# schematic.net
KiCad netlist of a schematic drawn in Altium Designer
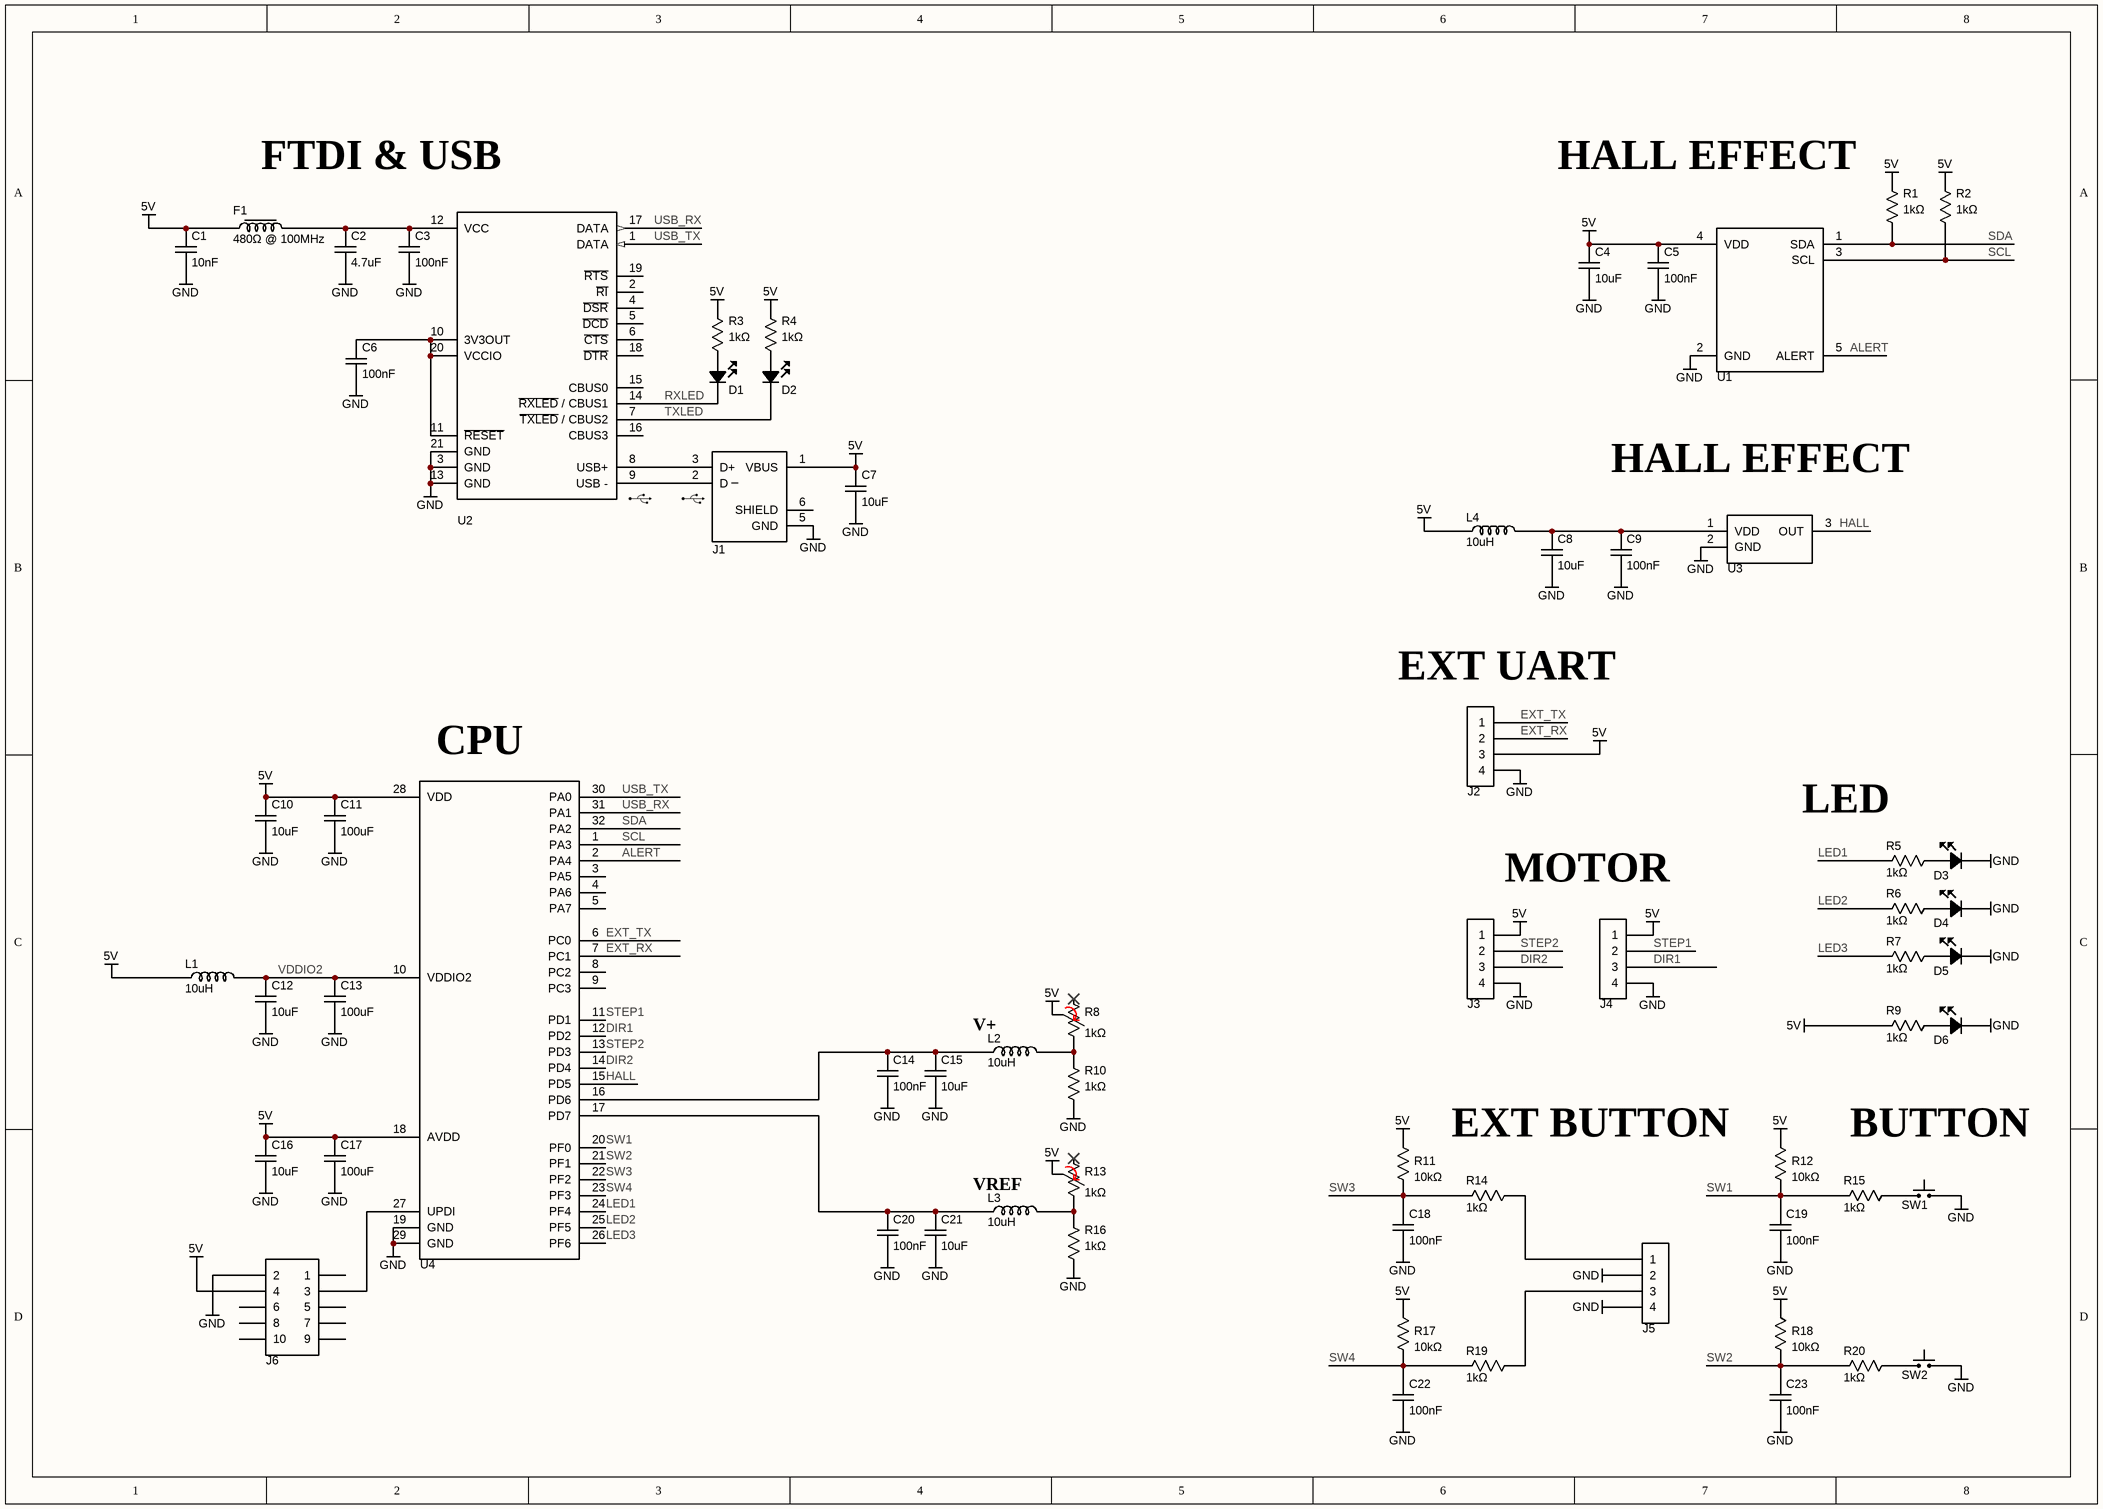
[diagram p0: schematic.SchDoc]

(export (version "E")
  (design (tool "Eeschema 10.0.6"))
  (components
    (comp (ref "C1")
      (value "10nF")
      (footprint "capacitor 0603")
      (description "Capacitor 0603")
      (fields (field (name "Comment") "passive_5"))
      (libsource (lib "passive") (part "passive_5"))
    )
    (comp (ref "C2")
      (value "4.7uF")
      (footprint "capacitor 0603")
      (description "Capacitor 0603")
      (fields (field (name "Comment") "passive_5"))
      (libsource (lib "passive") (part "passive_5"))
    )
    (comp (ref "C3")
      (value "100nF")
      (footprint "capacitor 0603")
      (description "Capacitor 0603")
      (fields (field (name "Comment") "passive_5"))
      (libsource (lib "passive") (part "passive_5"))
    )
    (comp (ref "C4")
      (value "10uF")
      (footprint "capacitor 0603")
      (description "Capacitor 0603")
      (fields (field (name "Comment") "passive_5"))
      (libsource (lib "passive") (part "passive_5"))
    )
    (comp (ref "C5")
      (value "100nF")
      (footprint "capacitor 0603")
      (description "Capacitor 0603")
      (fields (field (name "Comment") "passive_5"))
      (libsource (lib "passive") (part "passive_5"))
    )
    (comp (ref "C6")
      (value "100nF")
      (footprint "capacitor 0603")
      (description "Capacitor 0603")
      (fields (field (name "Comment") "passive_5"))
      (libsource (lib "passive") (part "passive_5"))
    )
    (comp (ref "C7")
      (value "10uF")
      (footprint "capacitor 0603")
      (description "Capacitor 0603")
      (fields (field (name "Comment") "passive_5"))
      (libsource (lib "passive") (part "passive_5"))
    )
    (comp (ref "C8")
      (value "10uF")
      (footprint "capacitor 0603")
      (description "Capacitor 0603")
      (fields (field (name "Comment") "passive_5"))
      (libsource (lib "passive") (part "passive_5"))
    )
    (comp (ref "C9")
      (value "100nF")
      (footprint "capacitor 0603")
      (description "Capacitor 0603")
      (fields (field (name "Comment") "passive_5"))
      (libsource (lib "passive") (part "passive_5"))
    )
    (comp (ref "C10")
      (value "10uF")
      (footprint "capacitor 0603")
      (description "Capacitor 0603")
      (fields (field (name "Comment") "passive_5"))
      (libsource (lib "passive") (part "passive_5"))
    )
    (comp (ref "C11")
      (value "100uF")
      (footprint "capacitor 0603")
      (description "Capacitor 0603")
      (fields (field (name "Comment") "passive_5"))
      (libsource (lib "passive") (part "passive_5"))
    )
    (comp (ref "C12")
      (value "10uF")
      (footprint "capacitor 0603")
      (description "Capacitor 0603")
      (fields (field (name "Comment") "passive_5"))
      (libsource (lib "passive") (part "passive_5"))
    )
    (comp (ref "C13")
      (value "100uF")
      (footprint "capacitor 0603")
      (description "Capacitor 0603")
      (fields (field (name "Comment") "passive_5"))
      (libsource (lib "passive") (part "passive_5"))
    )
    (comp (ref "C14")
      (value "100nF")
      (footprint "capacitor 0603")
      (description "Capacitor 0603")
      (fields (field (name "Comment") "passive_5"))
      (libsource (lib "passive") (part "passive_5"))
    )
    (comp (ref "C15")
      (value "10uF")
      (footprint "capacitor 0603")
      (description "Capacitor 0603")
      (fields (field (name "Comment") "passive_5"))
      (libsource (lib "passive") (part "passive_5"))
    )
    (comp (ref "C16")
      (value "10uF")
      (footprint "capacitor 0603")
      (description "Capacitor 0603")
      (fields (field (name "Comment") "passive_5"))
      (libsource (lib "passive") (part "passive_5"))
    )
    (comp (ref "C17")
      (value "100uF")
      (footprint "capacitor 0603")
      (description "Capacitor 0603")
      (fields (field (name "Comment") "passive_5"))
      (libsource (lib "passive") (part "passive_5"))
    )
    (comp (ref "C18")
      (value "100nF")
      (footprint "capacitor 0603")
      (description "Capacitor 0603")
      (fields (field (name "Comment") "passive_5"))
      (libsource (lib "passive") (part "passive_5"))
    )
    (comp (ref "C19")
      (value "100nF")
      (footprint "capacitor 0603")
      (description "Capacitor 0603")
      (fields (field (name "Comment") "passive_5"))
      (libsource (lib "passive") (part "passive_5"))
    )
    (comp (ref "C20")
      (value "100nF")
      (footprint "capacitor 0603")
      (description "Capacitor 0603")
      (fields (field (name "Comment") "passive_5"))
      (libsource (lib "passive") (part "passive_5"))
    )
    (comp (ref "C21")
      (value "10uF")
      (footprint "capacitor 0603")
      (description "Capacitor 0603")
      (fields (field (name "Comment") "passive_5"))
      (libsource (lib "passive") (part "passive_5"))
    )
    (comp (ref "C22")
      (value "100nF")
      (footprint "capacitor 0603")
      (description "Capacitor 0603")
      (fields (field (name "Comment") "passive_5"))
      (libsource (lib "passive") (part "passive_5"))
    )
    (comp (ref "C23")
      (value "100nF")
      (footprint "capacitor 0603")
      (description "Capacitor 0603")
      (fields (field (name "Comment") "passive_5"))
      (libsource (lib "passive") (part "passive_5"))
    )
    (comp (ref "D1")
      (value "LED Red")
      (footprint "LED 0603 red")
      (description "LED 0603 red")
      (libsource (lib "diode") (part "diode_0"))
    )
    (comp (ref "D2")
      (value "LED Red")
      (footprint "LED 0603 red")
      (description "LED 0603 red")
      (libsource (lib "diode") (part "diode_0"))
    )
    (comp (ref "D3")
      (value "LED Red")
      (footprint "LED 0603 red")
      (description "LED 0603 red")
      (libsource (lib "diode") (part "diode_0"))
    )
    (comp (ref "D4")
      (value "LED Red")
      (footprint "LED 0603 red")
      (description "LED 0603 red")
      (libsource (lib "diode") (part "diode_0"))
    )
    (comp (ref "D5")
      (value "LED Red")
      (footprint "LED 0603 red")
      (description "LED 0603 red")
      (libsource (lib "diode") (part "diode_0"))
    )
    (comp (ref "D6")
      (value "LED Red")
      (footprint "LED 0603 red")
      (description "LED 0603 red")
      (libsource (lib "diode") (part "diode_0"))
    )
    (comp (ref "F1")
      (value "480Ω @ 100MHz")
      (footprint "ferrit bead 0603")
      (description "Ferrite bead 0603")
      (fields (field (name "Comment") "passive_8"))
      (libsource (lib "passive") (part "passive_8"))
    )
    (comp (ref "J1")
      (value "USB micro B")
      (footprint "USB mico B female")
      (description "USB micro B (2.0)")
      (libsource (lib "connector") (part "connector_34"))
    )
    (comp (ref "J2")
      (value "Header 2.54mm")
      (footprint "TB001-500-04BE")
      (description "Screw Terminal")
      (libsource (lib "connector") (part "connector_53"))
    )
    (comp (ref "J3")
      (value "Header 2.54mm")
      (footprint "TB001-500-04BE")
      (description "Screw Terminal")
      (libsource (lib "connector") (part "connector_53"))
    )
    (comp (ref "J4")
      (value "Header 2.54mm")
      (footprint "TB001-500-04BE")
      (description "Screw Terminal")
      (libsource (lib "connector") (part "connector_53"))
    )
    (comp (ref "J5")
      (value "Header 2.54mm")
      (footprint "TB001-500-04BE")
      (description "Screw Terminal")
      (libsource (lib "") (part "connector_53_1"))
    )
    (comp (ref "J6")
      (value "Header 1.27mm")
      (footprint "header male 2x5, pitch 1.27mm")
      (description "Header male 2x5, pitch 1.27mm")
      (libsource (lib "connector") (part "connector_17"))
    )
    (comp (ref "L1")
      (value "10uH")
      (footprint "inductor 0603")
      (description "Inductor 0603")
      (fields (field (name "Comment") "passive_9"))
      (libsource (lib "") (part "passive_9_1"))
    )
    (comp (ref "L2")
      (value "10uH")
      (footprint "inductor 0603")
      (description "Inductor 0603")
      (fields (field (name "Comment") "passive_9"))
      (libsource (lib "passive") (part "passive_9"))
    )
    (comp (ref "L3")
      (value "10uH")
      (footprint "inductor 0603")
      (description "Inductor 0603")
      (fields (field (name "Comment") "passive_9"))
      (libsource (lib "passive") (part "passive_9"))
    )
    (comp (ref "L4")
      (value "10uH")
      (footprint "inductor 0603")
      (description "Inductor 0603")
      (fields (field (name "Comment") "passive_9"))
      (libsource (lib "") (part "passive_9_1"))
    )
    (comp (ref "R1")
      (value "1kΩ")
      (footprint "resistor 0603")
      (description "Resistor 0603")
      (fields (field (name "Comment") "passive_2"))
      (libsource (lib "passive") (part "passive_2"))
    )
    (comp (ref "R2")
      (value "1kΩ")
      (footprint "resistor 0603")
      (description "Resistor 0603")
      (fields (field (name "Comment") "passive_2"))
      (libsource (lib "passive") (part "passive_2"))
    )
    (comp (ref "R3")
      (value "1kΩ")
      (footprint "resistor 0603")
      (description "Resistor 0603")
      (fields (field (name "Comment") "passive_2"))
      (libsource (lib "passive") (part "passive_2"))
    )
    (comp (ref "R4")
      (value "1kΩ")
      (footprint "resistor 0603")
      (description "Resistor 0603")
      (fields (field (name "Comment") "passive_2"))
      (libsource (lib "passive") (part "passive_2"))
    )
    (comp (ref "R5")
      (value "1kΩ")
      (footprint "resistor 0603")
      (description "Resistor 0603")
      (fields (field (name "Comment") "passive_2"))
      (libsource (lib "passive") (part "passive_2"))
    )
    (comp (ref "R6")
      (value "1kΩ")
      (footprint "resistor 0603")
      (description "Resistor 0603")
      (fields (field (name "Comment") "passive_2"))
      (libsource (lib "passive") (part "passive_2"))
    )
    (comp (ref "R7")
      (value "1kΩ")
      (footprint "resistor 0603")
      (description "Resistor 0603")
      (fields (field (name "Comment") "passive_2"))
      (libsource (lib "passive") (part "passive_2"))
    )
    (comp (ref "R8")
      (value "1kΩ")
      (footprint "POT")
      (description "Potmeter")
      (fields (field (name "Comment") "passive_13"))
      (libsource (lib "passive") (part "passive_13"))
    )
    (comp (ref "R9")
      (value "1kΩ")
      (footprint "resistor 0603")
      (description "Resistor 0603")
      (fields (field (name "Comment") "passive_2"))
      (libsource (lib "passive") (part "passive_2"))
    )
    (comp (ref "R10")
      (value "1kΩ")
      (footprint "resistor 0603")
      (description "Resistor 0603")
      (fields (field (name "Comment") "passive_2"))
      (libsource (lib "passive") (part "passive_2"))
    )
    (comp (ref "R11")
      (value "10kΩ")
      (footprint "resistor 0603")
      (description "Resistor 0603")
      (fields (field (name "Comment") "passive_2"))
      (libsource (lib "passive") (part "passive_2"))
    )
    (comp (ref "R12")
      (value "10kΩ")
      (footprint "resistor 0603")
      (description "Resistor 0603")
      (fields (field (name "Comment") "passive_2"))
      (libsource (lib "passive") (part "passive_2"))
    )
    (comp (ref "R13")
      (value "1kΩ")
      (footprint "POT")
      (description "Potmeter")
      (fields (field (name "Comment") "passive_13"))
      (libsource (lib "passive") (part "passive_13"))
    )
    (comp (ref "R14")
      (value "1kΩ")
      (footprint "resistor 0603")
      (description "Resistor 0603")
      (fields (field (name "Comment") "passive_2"))
      (libsource (lib "passive") (part "passive_2"))
    )
    (comp (ref "R15")
      (value "1kΩ")
      (footprint "resistor 0603")
      (description "Resistor 0603")
      (fields (field (name "Comment") "passive_2"))
      (libsource (lib "passive") (part "passive_2"))
    )
    (comp (ref "R16")
      (value "1kΩ")
      (footprint "resistor 0603")
      (description "Resistor 0603")
      (fields (field (name "Comment") "passive_2"))
      (libsource (lib "passive") (part "passive_2"))
    )
    (comp (ref "R17")
      (value "10kΩ")
      (footprint "resistor 0603")
      (description "Resistor 0603")
      (fields (field (name "Comment") "passive_2"))
      (libsource (lib "passive") (part "passive_2"))
    )
    (comp (ref "R18")
      (value "10kΩ")
      (footprint "resistor 0603")
      (description "Resistor 0603")
      (fields (field (name "Comment") "passive_2"))
      (libsource (lib "passive") (part "passive_2"))
    )
    (comp (ref "R19")
      (value "1kΩ")
      (footprint "resistor 0603")
      (description "Resistor 0603")
      (fields (field (name "Comment") "passive_2"))
      (libsource (lib "passive") (part "passive_2"))
    )
    (comp (ref "R20")
      (value "1kΩ")
      (footprint "resistor 0603")
      (description "Resistor 0603")
      (fields (field (name "Comment") "passive_2"))
      (libsource (lib "passive") (part "passive_2"))
    )
    (comp (ref "SW1")
      (value "sensor_3")
      (footprint "KMR621NG LFS")
      (description "Tactile switch SMD, tiny")
      (libsource (lib "sensor") (part "sensor_3"))
    )
    (comp (ref "SW2")
      (value "sensor_3")
      (footprint "KMR621NG LFS")
      (description "Tactile switch SMD, tiny")
      (libsource (lib "sensor") (part "sensor_3"))
    )
    (comp (ref "U1")
      (value "ic_14")
      (footprint "SI7210-B-00-IVR")
      (description "Hall-effect")
      (libsource (lib "integrated-circuit") (part "ic_14"))
    )
    (comp (ref "U2")
      (value "FTDI")
      (footprint "FT231XQ-R")
      (description "USB to UART converter, FTDI, single, 20 pins, QFN")
      (libsource (lib "integrated-circuit") (part "ic_1"))
    )
    (comp (ref "U3")
      (value "ic_15")
      (footprint "SS495A1")
      (description "SS495A1")
      (libsource (lib "integrated-circuit") (part "ic_15"))
    )
    (comp (ref "U4")
      (value "cpu_7")
      (footprint "AVRxxDB32")
      (description "AVRxxDB32")
      (libsource (lib "cpu") (part "cpu_7"))
    )
  )
  (nets
    (net (code "1") (name "/ALERT") (class "Default")
      (node (ref "U1") (pin "5") (pinfunction "ALERT_5") (pintype "passive"))
      (node (ref "U4") (pin "2") (pinfunction "PA4_2") (pintype "passive"))
    )
    (net (code "2") (name "/DIR1") (class "Default")
      (node (ref "J4") (pin "3") (pinfunction "3_3") (pintype "passive"))
      (node (ref "U4") (pin "12") (pinfunction "PD2_12") (pintype "passive"))
    )
    (net (code "3") (name "/DIR2") (class "Default")
      (node (ref "J3") (pin "3") (pinfunction "3_3") (pintype "passive"))
      (node (ref "U4") (pin "14") (pinfunction "PD4_14") (pintype "passive"))
    )
    (net (code "4") (name "/EXT_RX") (class "Default")
      (node (ref "J2") (pin "2") (pinfunction "2_2") (pintype "passive"))
      (node (ref "U4") (pin "7") (pinfunction "PC1_7") (pintype "passive"))
    )
    (net (code "5") (name "/EXT_TX") (class "Default")
      (node (ref "J2") (pin "1") (pinfunction "1_1") (pintype "passive"))
      (node (ref "U4") (pin "6") (pinfunction "PC0_6") (pintype "passive"))
    )
    (net (code "6") (name "/HALL") (class "Default")
      (node (ref "U3") (pin "3") (pinfunction "OUT_3") (pintype "passive"))
      (node (ref "U4") (pin "15") (pinfunction "PD5_15") (pintype "passive"))
    )
    (net (code "7") (name "/LED1") (class "Default")
      (node (ref "R5") (pin "2") (pinfunction "2_2") (pintype "passive"))
      (node (ref "U4") (pin "24") (pinfunction "PF4_24") (pintype "passive"))
    )
    (net (code "8") (name "/LED2") (class "Default")
      (node (ref "R6") (pin "2") (pinfunction "2_2") (pintype "passive"))
      (node (ref "U4") (pin "25") (pinfunction "PF5_25") (pintype "passive"))
    )
    (net (code "9") (name "/LED3") (class "Default")
      (node (ref "R7") (pin "2") (pinfunction "2_2") (pintype "passive"))
      (node (ref "U4") (pin "26") (pinfunction "PF6_26") (pintype "passive"))
    )
    (net (code "10") (name "/RXLED") (class "Default")
      (node (ref "D1") (pin "2") (pinfunction "2_2") (pintype "passive"))
      (node (ref "U2") (pin "14") (pinfunction "~{RXLED}_/_CBUS1_14") (pintype "passive"))
    )
    (net (code "11") (name "/SCL") (class "Default")
      (node (ref "R2") (pin "1") (pintype "passive"))
      (node (ref "U1") (pin "3") (pinfunction "SCL_3") (pintype "passive"))
      (node (ref "U4") (pin "1") (pinfunction "PA3_1") (pintype "passive"))
    )
    (net (code "12") (name "/SDA") (class "Default")
      (node (ref "R1") (pin "1") (pintype "passive"))
      (node (ref "U1") (pin "1") (pinfunction "SDA_1") (pintype "passive"))
      (node (ref "U4") (pin "32") (pinfunction "PA2_32") (pintype "passive"))
    )
    (net (code "13") (name "/STEP1") (class "Default")
      (node (ref "J4") (pin "2") (pinfunction "2_2") (pintype "passive"))
      (node (ref "U4") (pin "11") (pinfunction "PD1_11") (pintype "passive"))
    )
    (net (code "14") (name "/STEP2") (class "Default")
      (node (ref "J3") (pin "2") (pinfunction "2_2") (pintype "passive"))
      (node (ref "U4") (pin "13") (pinfunction "PD3_13") (pintype "passive"))
    )
    (net (code "15") (name "/SW1") (class "Default")
      (node (ref "C19") (pin "2") (pinfunction "2_2") (pintype "passive"))
      (node (ref "R12") (pin "2") (pinfunction "2_2") (pintype "passive"))
      (node (ref "R15") (pin "2") (pinfunction "2_2") (pintype "passive"))
      (node (ref "U4") (pin "20") (pinfunction "PF0_20") (pintype "passive"))
    )
    (net (code "16") (name "/SW2") (class "Default")
      (node (ref "C23") (pin "2") (pinfunction "2_2") (pintype "passive"))
      (node (ref "R18") (pin "2") (pinfunction "2_2") (pintype "passive"))
      (node (ref "R20") (pin "2") (pinfunction "2_2") (pintype "passive"))
      (node (ref "U4") (pin "21") (pinfunction "PF1_21") (pintype "passive"))
    )
    (net (code "17") (name "/SW3") (class "Default")
      (node (ref "C18") (pin "2") (pinfunction "2_2") (pintype "passive"))
      (node (ref "R11") (pin "2") (pinfunction "2_2") (pintype "passive"))
      (node (ref "R14") (pin "2") (pinfunction "2_2") (pintype "passive"))
      (node (ref "U4") (pin "22") (pinfunction "PF2_22") (pintype "passive"))
    )
    (net (code "18") (name "/SW4") (class "Default")
      (node (ref "C22") (pin "2") (pinfunction "2_2") (pintype "passive"))
      (node (ref "R17") (pin "2") (pinfunction "2_2") (pintype "passive"))
      (node (ref "R19") (pin "2") (pinfunction "2_2") (pintype "passive"))
      (node (ref "U4") (pin "23") (pinfunction "PF3_23") (pintype "passive"))
    )
    (net (code "19") (name "/TXLED") (class "Default")
      (node (ref "D2") (pin "2") (pinfunction "2_2") (pintype "passive"))
      (node (ref "U2") (pin "7") (pinfunction "~{TXLED}_/_CBUS2_7") (pintype "passive"))
    )
    (net (code "20") (name "/USB_RX") (class "Default")
      (node (ref "U2") (pin "17") (pinfunction "DATA_17") (pintype "passive"))
      (node (ref "U4") (pin "31") (pinfunction "PA1_31") (pintype "passive"))
    )
    (net (code "21") (name "/USB_TX") (class "Default")
      (node (ref "U2") (pin "1") (pinfunction "DATA_1") (pintype "passive"))
      (node (ref "U4") (pin "30") (pinfunction "PA0_30") (pintype "passive"))
    )
    (net (code "22") (name "/VDDIO2") (class "Default")
      (node (ref "C12") (pin "2") (pinfunction "2_2") (pintype "passive"))
      (node (ref "C13") (pin "2") (pinfunction "2_2") (pintype "passive"))
      (node (ref "L1") (pin "2") (pinfunction "2_2") (pintype "passive"))
      (node (ref "U4") (pin "10") (pinfunction "VDDIO2_10") (pintype "passive"))
    )
    (net (code "23") (name "5V") (class "Default")
      (node (ref "C1") (pin "2") (pinfunction "2_2") (pintype "passive"))
      (node (ref "C10") (pin "2") (pinfunction "2_2") (pintype "passive"))
      (node (ref "C11") (pin "2") (pinfunction "2_2") (pintype "passive"))
      (node (ref "C16") (pin "2") (pinfunction "2_2") (pintype "passive"))
      (node (ref "C17") (pin "2") (pinfunction "2_2") (pintype "passive"))
      (node (ref "C4") (pin "2") (pinfunction "2_2") (pintype "passive"))
      (node (ref "C5") (pin "2") (pinfunction "2_2") (pintype "passive"))
      (node (ref "C7") (pin "2") (pinfunction "2_2") (pintype "passive"))
      (node (ref "F1") (pin "1") (pintype "passive"))
      (node (ref "J1") (pin "1") (pinfunction "VBUS_1") (pintype "passive"))
      (node (ref "J2") (pin "3") (pinfunction "3_3") (pintype "passive"))
      (node (ref "J3") (pin "1") (pinfunction "1_1") (pintype "passive"))
      (node (ref "J4") (pin "1") (pinfunction "1_1") (pintype "passive"))
      (node (ref "J6") (pin "4") (pinfunction "4_4") (pintype "passive"))
      (node (ref "L1") (pin "1") (pintype "passive"))
      (node (ref "L4") (pin "1") (pintype "passive"))
      (node (ref "R1") (pin "2") (pinfunction "2_2") (pintype "passive"))
      (node (ref "R11") (pin "1") (pintype "passive"))
      (node (ref "R12") (pin "1") (pintype "passive"))
      (node (ref "R13") (pin "2") (pintype "passive"))
      (node (ref "R17") (pin "1") (pintype "passive"))
      (node (ref "R18") (pin "1") (pintype "passive"))
      (node (ref "R2") (pin "2") (pinfunction "2_2") (pintype "passive"))
      (node (ref "R3") (pin "2") (pinfunction "2_2") (pintype "passive"))
      (node (ref "R4") (pin "2") (pinfunction "2_2") (pintype "passive"))
      (node (ref "R8") (pin "2") (pintype "passive"))
      (node (ref "R9") (pin "2") (pinfunction "2_2") (pintype "passive"))
      (node (ref "U1") (pin "4") (pinfunction "VDD_4") (pintype "passive"))
      (node (ref "U4") (pin "18") (pinfunction "AVDD_18") (pintype "passive"))
      (node (ref "U4") (pin "28") (pinfunction "VDD_28") (pintype "passive"))
    )
    (net (code "24") (name "GND") (class "Default")
      (node (ref "C1") (pin "1") (pinfunction "1_1") (pintype "passive"))
      (node (ref "C10") (pin "1") (pinfunction "1_1") (pintype "passive"))
      (node (ref "C11") (pin "1") (pinfunction "1_1") (pintype "passive"))
      (node (ref "C12") (pin "1") (pinfunction "1_1") (pintype "passive"))
      (node (ref "C13") (pin "1") (pinfunction "1_1") (pintype "passive"))
      (node (ref "C14") (pin "1") (pinfunction "1_1") (pintype "passive"))
      (node (ref "C15") (pin "1") (pinfunction "1_1") (pintype "passive"))
      (node (ref "C16") (pin "1") (pinfunction "1_1") (pintype "passive"))
      (node (ref "C17") (pin "1") (pinfunction "1_1") (pintype "passive"))
      (node (ref "C18") (pin "1") (pinfunction "1_1") (pintype "passive"))
      (node (ref "C19") (pin "1") (pinfunction "1_1") (pintype "passive"))
      (node (ref "C2") (pin "1") (pinfunction "1_1") (pintype "passive"))
      (node (ref "C20") (pin "1") (pinfunction "1_1") (pintype "passive"))
      (node (ref "C21") (pin "1") (pinfunction "1_1") (pintype "passive"))
      (node (ref "C22") (pin "1") (pinfunction "1_1") (pintype "passive"))
      (node (ref "C23") (pin "1") (pinfunction "1_1") (pintype "passive"))
      (node (ref "C3") (pin "1") (pinfunction "1_1") (pintype "passive"))
      (node (ref "C4") (pin "1") (pinfunction "1_1") (pintype "passive"))
      (node (ref "C5") (pin "1") (pinfunction "1_1") (pintype "passive"))
      (node (ref "C6") (pin "1") (pinfunction "1_1") (pintype "passive"))
      (node (ref "C7") (pin "1") (pinfunction "1_1") (pintype "passive"))
      (node (ref "C8") (pin "1") (pinfunction "1_1") (pintype "passive"))
      (node (ref "C9") (pin "1") (pinfunction "1_1") (pintype "passive"))
      (node (ref "D3") (pin "2") (pinfunction "2_2") (pintype "passive"))
      (node (ref "D4") (pin "2") (pinfunction "2_2") (pintype "passive"))
      (node (ref "D5") (pin "2") (pinfunction "2_2") (pintype "passive"))
      (node (ref "D6") (pin "2") (pinfunction "2_2") (pintype "passive"))
      (node (ref "J1") (pin "5") (pinfunction "GND_5") (pintype "passive"))
      (node (ref "J2") (pin "4") (pinfunction "4_4") (pintype "passive"))
      (node (ref "J3") (pin "4") (pinfunction "4_4") (pintype "passive"))
      (node (ref "J4") (pin "4") (pinfunction "4_4") (pintype "passive"))
      (node (ref "J5") (pin "2") (pinfunction "2_2") (pintype "passive"))
      (node (ref "J5") (pin "4") (pinfunction "4_4") (pintype "passive"))
      (node (ref "J6") (pin "2") (pinfunction "2_2") (pintype "passive"))
      (node (ref "R10") (pin "1") (pintype "passive"))
      (node (ref "R16") (pin "1") (pintype "passive"))
      (node (ref "SW1") (pin "2") (pintype "passive"))
      (node (ref "SW2") (pin "2") (pintype "passive"))
      (node (ref "U1") (pin "2") (pinfunction "GND_2") (pintype "passive"))
      (node (ref "U2") (pin "13") (pinfunction "GND_13") (pintype "passive"))
      (node (ref "U2") (pin "21") (pinfunction "GND_21") (pintype "passive"))
      (node (ref "U2") (pin "3") (pinfunction "GND_3") (pintype "passive"))
      (node (ref "U3") (pin "2") (pinfunction "GND_2") (pintype "passive"))
      (node (ref "U4") (pin "19") (pinfunction "GND_19") (pintype "passive"))
      (node (ref "U4") (pin "29") (pinfunction "GND_29") (pintype "passive"))
    )
    (net (code "25") (name "Net-(D1-Pad1)") (class "Default")
      (node (ref "D1") (pin "1") (pinfunction "1_1") (pintype "passive"))
      (node (ref "R3") (pin "1") (pintype "passive"))
    )
    (net (code "26") (name "Net-(D2-Pad1)") (class "Default")
      (node (ref "D2") (pin "1") (pinfunction "1_1") (pintype "passive"))
      (node (ref "R4") (pin "1") (pintype "passive"))
    )
    (net (code "27") (name "Net-(D3-Pad1)") (class "Default")
      (node (ref "D3") (pin "1") (pinfunction "1_1") (pintype "passive"))
      (node (ref "R5") (pin "1") (pintype "passive"))
    )
    (net (code "28") (name "Net-(D4-Pad1)") (class "Default")
      (node (ref "D4") (pin "1") (pinfunction "1_1") (pintype "passive"))
      (node (ref "R6") (pin "1") (pintype "passive"))
    )
    (net (code "29") (name "Net-(D5-Pad1)") (class "Default")
      (node (ref "D5") (pin "1") (pinfunction "1_1") (pintype "passive"))
      (node (ref "R7") (pin "1") (pintype "passive"))
    )
    (net (code "30") (name "Net-(D6-Pad1)") (class "Default")
      (node (ref "D6") (pin "1") (pinfunction "1_1") (pintype "passive"))
      (node (ref "R9") (pin "1") (pintype "passive"))
    )
    (net (code "31") (name "Net-(J1-D)") (class "Default")
      (node (ref "J1") (pin "2") (pinfunction "D_2") (pintype "passive"))
      (node (ref "U2") (pin "9") (pinfunction "USB_-_9") (pintype "passive"))
    )
    (net (code "32") (name "Net-(J1-D+)") (class "Default")
      (node (ref "J1") (pin "3") (pinfunction "D+_3") (pintype "passive"))
      (node (ref "U2") (pin "8") (pinfunction "USB+_8") (pintype "passive"))
    )
    (net (code "33") (name "Net-(J5-Pad1)") (class "Default")
      (node (ref "J5") (pin "1") (pinfunction "1_1") (pintype "passive"))
      (node (ref "R14") (pin "1") (pintype "passive"))
    )
    (net (code "34") (name "Net-(J5-Pad3)") (class "Default")
      (node (ref "J5") (pin "3") (pinfunction "3_3") (pintype "passive"))
      (node (ref "R19") (pin "1") (pintype "passive"))
    )
    (net (code "35") (name "Net-(L2-Pad1)") (class "Default")
      (node (ref "L2") (pin "1") (pintype "passive"))
      (node (ref "R10") (pin "2") (pinfunction "2_2") (pintype "passive"))
      (node (ref "R8") (pin "3") (pintype "passive"))
    )
    (net (code "36") (name "Net-(L3-Pad1)") (class "Default")
      (node (ref "L3") (pin "1") (pintype "passive"))
      (node (ref "R13") (pin "3") (pintype "passive"))
      (node (ref "R16") (pin "2") (pinfunction "2_2") (pintype "passive"))
    )
    (net (code "37") (name "Net-(R15-Pad1)") (class "Default")
      (node (ref "R15") (pin "1") (pintype "passive"))
      (node (ref "SW1") (pin "1") (pintype "passive"))
    )
    (net (code "38") (name "Net-(R20-Pad1)") (class "Default")
      (node (ref "R20") (pin "1") (pintype "passive"))
      (node (ref "SW2") (pin "1") (pintype "passive"))
    )
    (net (code "39") (name "Net-(U2-3V3OUT)") (class "Default")
      (node (ref "C6") (pin "2") (pinfunction "2_2") (pintype "passive"))
      (node (ref "U2") (pin "10") (pinfunction "3V3OUT_10") (pintype "passive"))
      (node (ref "U2") (pin "11") (pinfunction "~{RESET}_11") (pintype "passive"))
      (node (ref "U2") (pin "20") (pinfunction "VCCIO_20") (pintype "passive"))
    )
    (net (code "40") (name "Net-(U2-VCC)") (class "Default")
      (node (ref "C2") (pin "2") (pinfunction "2_2") (pintype "passive"))
      (node (ref "C3") (pin "2") (pinfunction "2_2") (pintype "passive"))
      (node (ref "F1") (pin "2") (pinfunction "2_2") (pintype "passive"))
      (node (ref "U2") (pin "12") (pinfunction "VCC_12") (pintype "passive"))
    )
    (net (code "41") (name "Net-(U3-VDD)") (class "Default")
      (node (ref "C8") (pin "2") (pinfunction "2_2") (pintype "passive"))
      (node (ref "C9") (pin "2") (pinfunction "2_2") (pintype "passive"))
      (node (ref "L4") (pin "2") (pinfunction "2_2") (pintype "passive"))
      (node (ref "U3") (pin "1") (pinfunction "VDD_1") (pintype "passive"))
    )
    (net (code "42") (name "Net-(U4-PD6)") (class "Default")
      (node (ref "C14") (pin "2") (pinfunction "2_2") (pintype "passive"))
      (node (ref "C15") (pin "2") (pinfunction "2_2") (pintype "passive"))
      (node (ref "L2") (pin "2") (pinfunction "2_2") (pintype "passive"))
      (node (ref "U4") (pin "16") (pinfunction "PD6_16") (pintype "passive"))
    )
    (net (code "43") (name "Net-(U4-PD7)") (class "Default")
      (node (ref "C20") (pin "2") (pinfunction "2_2") (pintype "passive"))
      (node (ref "C21") (pin "2") (pinfunction "2_2") (pintype "passive"))
      (node (ref "L3") (pin "2") (pinfunction "2_2") (pintype "passive"))
      (node (ref "U4") (pin "17") (pinfunction "PD7_17") (pintype "passive"))
    )
    (net (code "44") (name "Net-(U4-UPDI)") (class "Default")
      (node (ref "J6") (pin "3") (pinfunction "3_3") (pintype "passive"))
      (node (ref "U4") (pin "27") (pinfunction "UPDI_27") (pintype "passive"))
    )
    (net (code "45") (name "unconnected-(J1-SHIELD-Pad6)") (class "Default")
      (node (ref "J1") (pin "6") (pinfunction "SHIELD_6") (pintype "passive"))
    )
    (net (code "46") (name "unconnected-(J6-Pad1)") (class "Default")
      (node (ref "J6") (pin "1") (pinfunction "1_1") (pintype "passive"))
    )
    (net (code "47") (name "unconnected-(J6-Pad5)") (class "Default")
      (node (ref "J6") (pin "5") (pinfunction "5_5") (pintype "passive"))
    )
    (net (code "48") (name "unconnected-(J6-Pad6)") (class "Default")
      (node (ref "J6") (pin "6") (pinfunction "6_6") (pintype "passive"))
    )
    (net (code "49") (name "unconnected-(J6-Pad7)") (class "Default")
      (node (ref "J6") (pin "7") (pinfunction "7_7") (pintype "passive"))
    )
    (net (code "50") (name "unconnected-(J6-Pad8)") (class "Default")
      (node (ref "J6") (pin "8") (pinfunction "8_8") (pintype "passive"))
    )
    (net (code "51") (name "unconnected-(J6-Pad9)") (class "Default")
      (node (ref "J6") (pin "9") (pinfunction "9_9") (pintype "passive"))
    )
    (net (code "52") (name "unconnected-(J6-Pad10)") (class "Default")
      (node (ref "J6") (pin "10") (pinfunction "10_10") (pintype "passive"))
    )
    (net (code "53") (name "unconnected-(R8-Pad1)") (class "Default")
      (node (ref "R8") (pin "1") (pintype "passive+no_connect"))
    )
    (net (code "54") (name "unconnected-(R13-Pad1)") (class "Default")
      (node (ref "R13") (pin "1") (pintype "passive+no_connect"))
    )
    (net (code "55") (name "unconnected-(U2-CBUS0-Pad15)") (class "Default")
      (node (ref "U2") (pin "15") (pinfunction "CBUS0_15") (pintype "passive"))
    )
    (net (code "56") (name "unconnected-(U2-CBUS3-Pad16)") (class "Default")
      (node (ref "U2") (pin "16") (pinfunction "CBUS3_16") (pintype "passive"))
    )
    (net (code "57") (name "unconnected-(U2-~{CTS}-Pad6)") (class "Default")
      (node (ref "U2") (pin "6") (pinfunction "~{CTS}_6") (pintype "passive"))
    )
    (net (code "58") (name "unconnected-(U2-~{DCD}-Pad5)") (class "Default")
      (node (ref "U2") (pin "5") (pinfunction "~{DCD}_5") (pintype "passive"))
    )
    (net (code "59") (name "unconnected-(U2-~{DSR}-Pad4)") (class "Default")
      (node (ref "U2") (pin "4") (pinfunction "~{DSR}_4") (pintype "passive"))
    )
    (net (code "60") (name "unconnected-(U2-~{DTR}-Pad18)") (class "Default")
      (node (ref "U2") (pin "18") (pinfunction "~{DTR}_18") (pintype "passive"))
    )
    (net (code "61") (name "unconnected-(U2-~{RI}-Pad2)") (class "Default")
      (node (ref "U2") (pin "2") (pinfunction "~{RI}_2") (pintype "passive"))
    )
    (net (code "62") (name "unconnected-(U2-~{RTS}-Pad19)") (class "Default")
      (node (ref "U2") (pin "19") (pinfunction "~{RTS}_19") (pintype "passive"))
    )
    (net (code "63") (name "unconnected-(U4-PA5-Pad3)") (class "Default")
      (node (ref "U4") (pin "3") (pinfunction "PA5_3") (pintype "passive"))
    )
    (net (code "64") (name "unconnected-(U4-PA6-Pad4)") (class "Default")
      (node (ref "U4") (pin "4") (pinfunction "PA6_4") (pintype "passive"))
    )
    (net (code "65") (name "unconnected-(U4-PA7-Pad5)") (class "Default")
      (node (ref "U4") (pin "5") (pinfunction "PA7_5") (pintype "passive"))
    )
    (net (code "66") (name "unconnected-(U4-PC2-Pad8)") (class "Default")
      (node (ref "U4") (pin "8") (pinfunction "PC2_8") (pintype "passive"))
    )
    (net (code "67") (name "unconnected-(U4-PC3-Pad9)") (class "Default")
      (node (ref "U4") (pin "9") (pinfunction "PC3_9") (pintype "passive"))
    )
  )
)
